# IMU.net
KiCad netlist of a schematic drawn in Altium Designer
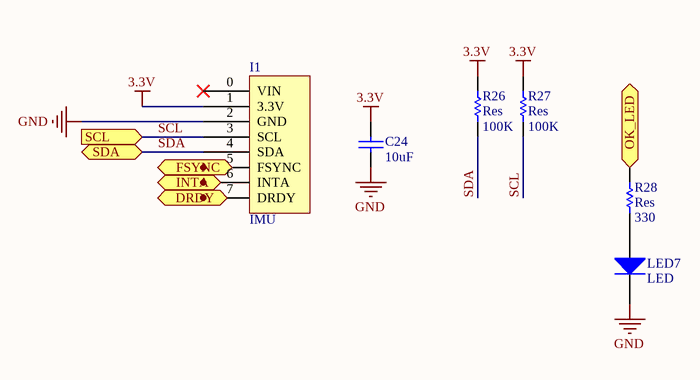
[diagram p0: IMU.SchDoc]

(export (version "E")
  (design (tool "Eeschema 10.0.6"))
  (components
    (comp (ref "C24")
      (value "10uF")
      (footprint "2012[0805]")
      (description "Capacitor")
      (fields (field (name "Comment") "Cap_UP") (field (name "PUBLISHER") "Altium Limited"))
      (libsource (lib "KN2CLib") (part "Cap_UP"))
    )
    (comp (ref "I1") (value "IMU") (footprint "IMU") (libsource (lib "IMU") (part "IMU")))
    (comp (ref "LED7")
      (value "LED")
      (footprint "2012[0805]")
      (description "1 Amp General Purpose Rectifier")
      (fields (field (name "PUBLISHER") "Altium Limited"))
      (libsource (lib "KN2CLib") (part "Diode"))
    )
    (comp (ref "R26")
      (value "Res")
      (footprint "2012[0805]")
      (description "Semiconductor Resistor")
      (fields (field (name "ALTIUM_VALUE") "100K") (field (name "PUBLISHER") "Altium Limited"))
      (libsource (lib "KN2CLib") (part "Res"))
    )
    (comp (ref "R27")
      (value "Res")
      (footprint "2012[0805]")
      (description "Semiconductor Resistor")
      (fields (field (name "ALTIUM_VALUE") "100K") (field (name "PUBLISHER") "Altium Limited"))
      (libsource (lib "KN2CLib") (part "Res"))
    )
    (comp (ref "R28")
      (value "Res")
      (footprint "2012[0805]")
      (description "Semiconductor Resistor")
      (fields (field (name "ALTIUM_VALUE") "330") (field (name "PUBLISHER") "Altium Limited"))
      (libsource (lib "KN2CLib") (part "Res"))
    )
  )
  (nets
    (net (code "4") (name "/OK_LED") (class "Default")
      (node (ref "R28") (pin "1") (pinfunction "1_1") (pintype "passive"))
    )
    (net (code "5") (name "/SCL") (class "Default")
      (node (ref "I1") (pin "3") (pinfunction "SCL_3") (pintype "passive"))
      (node (ref "R27") (pin "1") (pinfunction "1_1") (pintype "passive"))
    )
    (net (code "6") (name "/SDA") (class "Default")
      (node (ref "I1") (pin "4") (pinfunction "SDA_4") (pintype "passive"))
      (node (ref "R26") (pin "1") (pinfunction "1_1") (pintype "passive"))
    )
    (net (code "7") (name "3.3V") (class "Default")
      (node (ref "C24") (pin "2") (pinfunction "2_2") (pintype "passive"))
      (node (ref "I1") (pin "1") (pinfunction "3.3V_1") (pintype "passive"))
      (node (ref "R26") (pin "2") (pinfunction "2_2") (pintype "passive"))
      (node (ref "R27") (pin "2") (pinfunction "2_2") (pintype "passive"))
    )
    (net (code "8") (name "GND") (class "Default")
      (node (ref "C24") (pin "1") (pinfunction "1_1") (pintype "passive"))
      (node (ref "I1") (pin "2") (pinfunction "GND_2") (pintype "passive"))
      (node (ref "LED7") (pin "2") (pinfunction "K_2") (pintype "passive"))
    )
    (net (code "9") (name "Net-(LED7-A)") (class "Default")
      (node (ref "LED7") (pin "1") (pinfunction "A_1") (pintype "passive"))
      (node (ref "R28") (pin "2") (pinfunction "2_2") (pintype "passive"))
    )
    (net (code "10") (name "unconnected-(I1-DRDY-Pad7)") (class "Default")
      (node (ref "I1") (pin "7") (pinfunction "DRDY_7") (pintype "passive"))
    )
    (net (code "11") (name "unconnected-(I1-FSYNC-Pad5)") (class "Default")
      (node (ref "I1") (pin "5") (pinfunction "FSYNC_5") (pintype "passive"))
    )
    (net (code "12") (name "unconnected-(I1-INTA-Pad6)") (class "Default")
      (node (ref "I1") (pin "6") (pinfunction "INTA_6") (pintype "passive"))
    )
    (net (code "13") (name "unconnected-(I1-VIN-Pad0)") (class "Default")
      (node (ref "I1") (pin "0") (pinfunction "VIN_0") (pintype "passive+no_connect"))
    )
  )
)
